# FTDI.net
KiCad netlist of a schematic drawn in Altium Designer
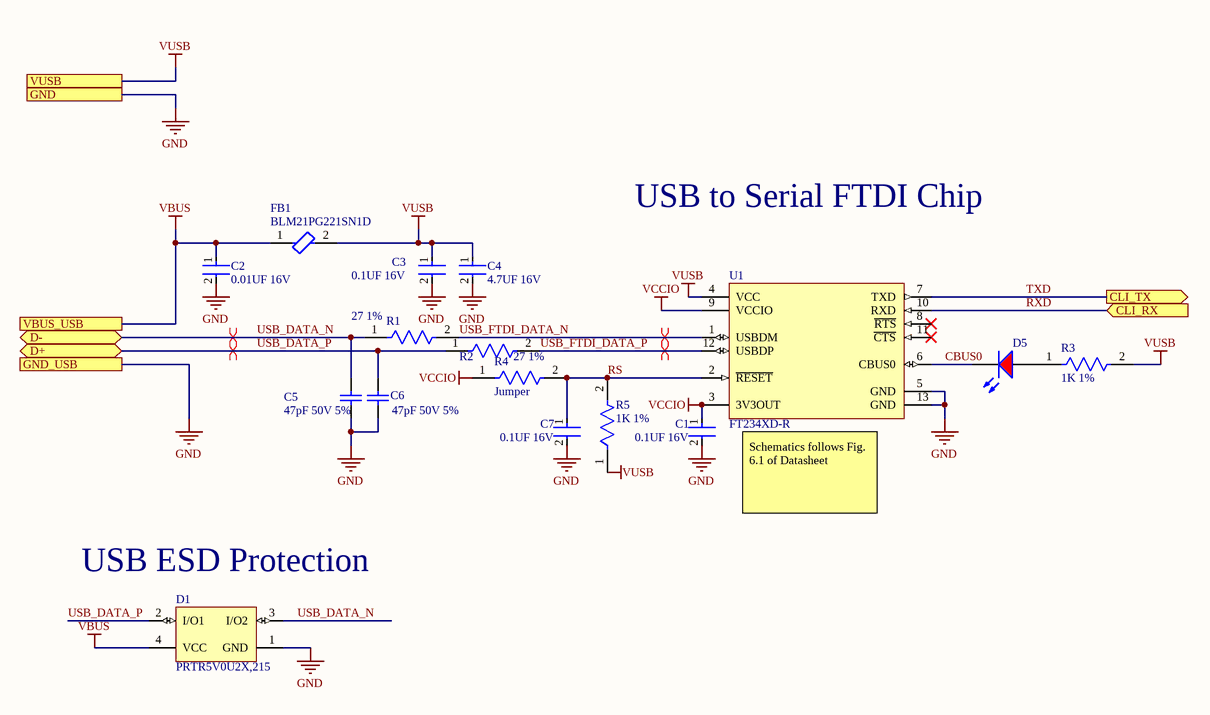
[diagram p0: FTDI.SchDoc]

(export (version "E")
  (design (tool "Eeschema 10.0.6"))
  (components
    (comp (ref "C1")
      (value "0.1UF 16V")
      (footprint "FP-CC0402-MFG")
      (description "CC0402 100 nF X7R 10.00% 25 V")
      (fields
        (field (name "MANUFACTURER PART NUMBER") "CC0402KPX7R8BB104")
        (field (name "MANUFACTURER") "YAGEO")
      )
      (libsource (lib "Altium Content Vault") (part "11868f565c42a9108669ba33697ecf6"))
    )
    (comp (ref "C2")
      (value "0.01UF 16V")
      (footprint "FP-CC0402-MFG")
      (description "CC0402 10 nF X7R 10.00% 16 V")
      (fields
        (field (name "TOLERANCE") "0.1")
        (field (name "OCTOPART") "https://octopart.com/cc0402kpx7r7bb103-yageo-12885102")
      )
      (libsource (lib "Altium Content Vault") (part "11868f565c42a9108669ba33697ecf6"))
    )
    (comp (ref "C3")
      (value "0.1UF 16V")
      (footprint "FP-CC0402-MFG")
      (description "CC0402 100 nF X7R 10.00% 25 V")
      (fields
        (field (name "MANUFACTURER PART NUMBER") "CC0402KPX7R8BB104")
        (field (name "MANUFACTURER") "YAGEO")
      )
      (libsource (lib "Altium Content Vault") (part "11868f565c42a9108669ba33697ecf6"))
    )
    (comp (ref "C4")
      (value "4.7UF 16V")
      (footprint "FP-CC0402-MFG")
      (description "CAP CER 4700PF 25V X7R 0402")
      (fields
        (field (name "MANUFACTURER PART NUMBER") "CC0402KRX7R8BB472")
        (field (name "MANUFACTURER") "YAGEO")
      )
      (libsource (lib "Altium Content Vault") (part "11868f565c42a9108669ba33697ecf6"))
    )
    (comp (ref "C5")
      (value "47pF 50V 5%")
      (footprint "0603_CAP")
      (description "Capacitor Surface Mount 0603 Footprint 47PF 50V 5% Tolerance Ceramic C0G")
      (fields (field (name "MANUFACTURER") "Various") (field (name "VOLTAGE") "50V"))
      (libsource (lib "University of Pennsylvania (ESE Labs)") (part "cap"))
    )
    (comp (ref "C6")
      (value "47pF 50V 5%")
      (footprint "0603_CAP")
      (description "Capacitor Surface Mount 0603 Footprint 47PF 50V 5% Tolerance Ceramic C0G")
      (fields (field (name "MANUFACTURER") "Various") (field (name "VOLTAGE") "50V"))
      (libsource (lib "University of Pennsylvania (ESE Labs)") (part "cap"))
    )
    (comp (ref "C7")
      (value "0.1UF 16V")
      (footprint "FP-CC0402-MFG")
      (description "CC0402 100 nF X7R 10.00% 25 V")
      (fields
        (field (name "MANUFACTURER PART NUMBER") "CC0402KPX7R8BB104")
        (field (name "MANUFACTURER") "YAGEO")
      )
      (libsource (lib "Altium Content Vault") (part "11868f565c42a9108669ba33697ecf6"))
    )
    (comp (ref "D1")
      (value "PRTR5V0U2X,215")
      (footprint "NXP-SOT143B-4_V")
      (fields (field (name "MANUFACTURER") "NXP Semiconductors"))
      (libsource (lib "Altium Content Vault") (part "NXP-PRTR5V0U2X,215-4"))
    )
    (comp (ref "D5")
      (value "LSM0805412V")
      (footprint "LED_0805_RED")
      (description "Single Color LED, RED, 0805")
      (libsource (lib "University of Pennsylvania (ESE Labs)") (part "LED-RED-AK-2"))
    )
    (comp (ref "FB1")
      (value "BLM21PG221SN1D")
      (footprint "FP-BLM21-0_2-t0_85-e0_5-IPC_B")
      (description "Chip Ferrite Bead, 0805, 220Ω @ 100MHz, 0.045Ω, 25%, 2A")
      (fields (field (name "TOLERANCE") "25%"))
      (libsource (lib "Altium Content Vault") (part "5f30dd21d616792df468990f7003faa"))
    )
    (comp (ref "R1")
      (value "27 1%")
      (footprint "FP-RMCF0603-IPC_B")
      (description "27Ω ±1% 0.1W 0603 Thick Film Chip Resistor AEC-Q200 compliant")
      (fields (field (name "TOLERANCE") "1%"))
      (libsource (lib "Altium Content Vault") (part "1029c3af85768c4190bb7ad29bc67b5"))
    )
    (comp (ref "R2")
      (value "27 1%")
      (footprint "FP-RMCF0603-IPC_B")
      (description "27Ω ±1% 0.1W 0603 Thick Film Chip Resistor AEC-Q200 compliant")
      (fields (field (name "TOLERANCE") "1%"))
      (libsource (lib "Altium Content Vault") (part "1029c3af85768c4190bb7ad29bc67b5"))
    )
    (comp (ref "R3")
      (value "1K 1%")
      (footprint "FP-RNCP0603-IPC_C")
      (description "1kΩ ±1% 0.125W 0603 High Power Anti-Sulfur Thin Film Chip Resistor")
      (fields (field (name "TOLERANCE") "1%"))
      (libsource (lib "Altium Content Vault") (part "1029c3af85768c4190bb7ad29bc67b5"))
    )
    (comp (ref "R4")
      (value "Jumper")
      (footprint "FP-RMCF0603-MFG")
      (description "RES 0 OHM JUMPER 1/10W 0603")
      (fields
        (field (name "MANUFACTURER PART NUMBER") "RMCF0603ZT0R00")
        (field (name "OCTOPART") "https://octopart.com/rmcf0603zt0r00-stackpole+electronics-19213618")
      )
      (libsource (lib "Altium Content Vault") (part "1029c3af85768c4190bb7ad29bc67b5"))
    )
    (comp (ref "R5")
      (value "1K 1%")
      (footprint "FP-RNCP0603-IPC_C")
      (description "1kΩ ±1% 0.125W 0603 High Power Anti-Sulfur Thin Film Chip Resistor")
      (fields (field (name "TOLERANCE") "1%"))
      (libsource (lib "Altium Content Vault") (part "1029c3af85768c4190bb7ad29bc67b5"))
    )
    (comp (ref "U1")
      (value "FT234XD-R")
      (footprint "FP-DFN-12-MFG")
      (description "USB Bridge, USB to UART USB 2.0 UART Interface 12-DFN (3x3)")
      (libsource (lib "University of Pennsylvania (ESE Labs)") (part "FT234-Symbol"))
    )
  )
  (nets
    (net (code "1") (name "/CBUS0") (class "Default")
      (node (ref "D5") (pin "K") (pinfunction "K_K") (pintype "passive"))
      (node (ref "U1") (pin "6") (pinfunction "CBUS0_6") (pintype "bidirectional"))
    )
    (net (code "2") (name "/RS") (class "Default")
      (node (ref "C7") (pin "1") (pinfunction "1_1") (pintype "passive"))
      (node (ref "R4") (pin "2") (pinfunction "2_2") (pintype "passive"))
      (node (ref "R5") (pin "2") (pinfunction "2_2") (pintype "passive"))
      (node (ref "U1") (pin "2") (pinfunction "~{RESET}_2") (pintype "input"))
    )
    (net (code "3") (name "/RXD") (class "Default")
      (node (ref "U1") (pin "10") (pinfunction "RXD_10") (pintype "input"))
    )
    (net (code "4") (name "/TXD") (class "Default")
      (node (ref "U1") (pin "7") (pinfunction "TXD_7") (pintype "output"))
    )
    (net (code "5") (name "/USB_DATA_N") (class "Default")
      (node (ref "C5") (pin "2") (pinfunction "2_2") (pintype "passive"))
      (node (ref "D1") (pin "3") (pinfunction "I/O2_3") (pintype "bidirectional"))
      (node (ref "R1") (pin "1") (pinfunction "1_1") (pintype "passive"))
    )
    (net (code "6") (name "/USB_DATA_P") (class "Default")
      (node (ref "C6") (pin "2") (pinfunction "2_2") (pintype "passive"))
      (node (ref "D1") (pin "2") (pinfunction "I/O1_2") (pintype "bidirectional"))
      (node (ref "R2") (pin "1") (pinfunction "1_1") (pintype "passive"))
    )
    (net (code "7") (name "/USB_FTDI_DATA_N") (class "Default")
      (node (ref "R1") (pin "2") (pinfunction "2_2") (pintype "passive"))
      (node (ref "U1") (pin "1") (pinfunction "USBDM_1") (pintype "bidirectional"))
    )
    (net (code "8") (name "/USB_FTDI_DATA_P") (class "Default")
      (node (ref "R2") (pin "2") (pinfunction "2_2") (pintype "passive"))
      (node (ref "U1") (pin "12") (pinfunction "USBDP_12") (pintype "bidirectional"))
    )
    (net (code "9") (name "GND") (class "Default")
      (node (ref "C1") (pin "2") (pinfunction "2_2") (pintype "passive"))
      (node (ref "C2") (pin "2") (pinfunction "2_2") (pintype "passive"))
      (node (ref "C3") (pin "2") (pinfunction "2_2") (pintype "passive"))
      (node (ref "C4") (pin "2") (pinfunction "2_2") (pintype "passive"))
      (node (ref "C5") (pin "1") (pinfunction "1_1") (pintype "passive"))
      (node (ref "C6") (pin "1") (pinfunction "1_1") (pintype "passive"))
      (node (ref "C7") (pin "2") (pinfunction "2_2") (pintype "passive"))
      (node (ref "D1") (pin "1") (pinfunction "GND_1") (pintype "power_in"))
      (node (ref "U1") (pin "13") (pinfunction "GND_13") (pintype "power_in"))
      (node (ref "U1") (pin "5") (pinfunction "GND_5") (pintype "power_in"))
    )
    (net (code "10") (name "Net-(D5-PadA)") (class "Default")
      (node (ref "D5") (pin "A") (pinfunction "A_A") (pintype "passive"))
      (node (ref "R3") (pin "1") (pinfunction "1_1") (pintype "passive"))
    )
    (net (code "11") (name "VBUS") (class "Default")
      (node (ref "C2") (pin "1") (pinfunction "1_1") (pintype "passive"))
      (node (ref "D1") (pin "4") (pinfunction "VCC_4") (pintype "power_in"))
      (node (ref "FB1") (pin "1") (pinfunction "1_1") (pintype "passive"))
    )
    (net (code "12") (name "VCCIO") (class "Default")
      (node (ref "C1") (pin "1") (pinfunction "1_1") (pintype "passive"))
      (node (ref "R4") (pin "1") (pinfunction "1_1") (pintype "passive"))
      (node (ref "U1") (pin "3") (pinfunction "3V3OUT_3") (pintype "power_in"))
      (node (ref "U1") (pin "9") (pinfunction "VCCIO_9") (pintype "power_in"))
    )
    (net (code "13") (name "VUSB") (class "Default")
      (node (ref "C3") (pin "1") (pinfunction "1_1") (pintype "passive"))
      (node (ref "C4") (pin "1") (pinfunction "1_1") (pintype "passive"))
      (node (ref "FB1") (pin "2") (pinfunction "2_2") (pintype "passive"))
      (node (ref "R3") (pin "2") (pinfunction "2_2") (pintype "passive"))
      (node (ref "R5") (pin "1") (pinfunction "1_1") (pintype "passive"))
      (node (ref "U1") (pin "4") (pinfunction "VCC_4") (pintype "power_in"))
    )
    (net (code "14") (name "unconnected-(U1-~{CTS}-Pad11)") (class "Default")
      (node (ref "U1") (pin "11") (pinfunction "~{CTS}_11") (pintype "input+no_connect"))
    )
    (net (code "15") (name "unconnected-(U1-~{RTS}-Pad8)") (class "Default")
      (node (ref "U1") (pin "8") (pinfunction "~{RTS}_8") (pintype "input+no_connect"))
    )
  )
)
